# 06_Clock_Configuration.net
KiCad netlist of a schematic drawn in Altium Designer
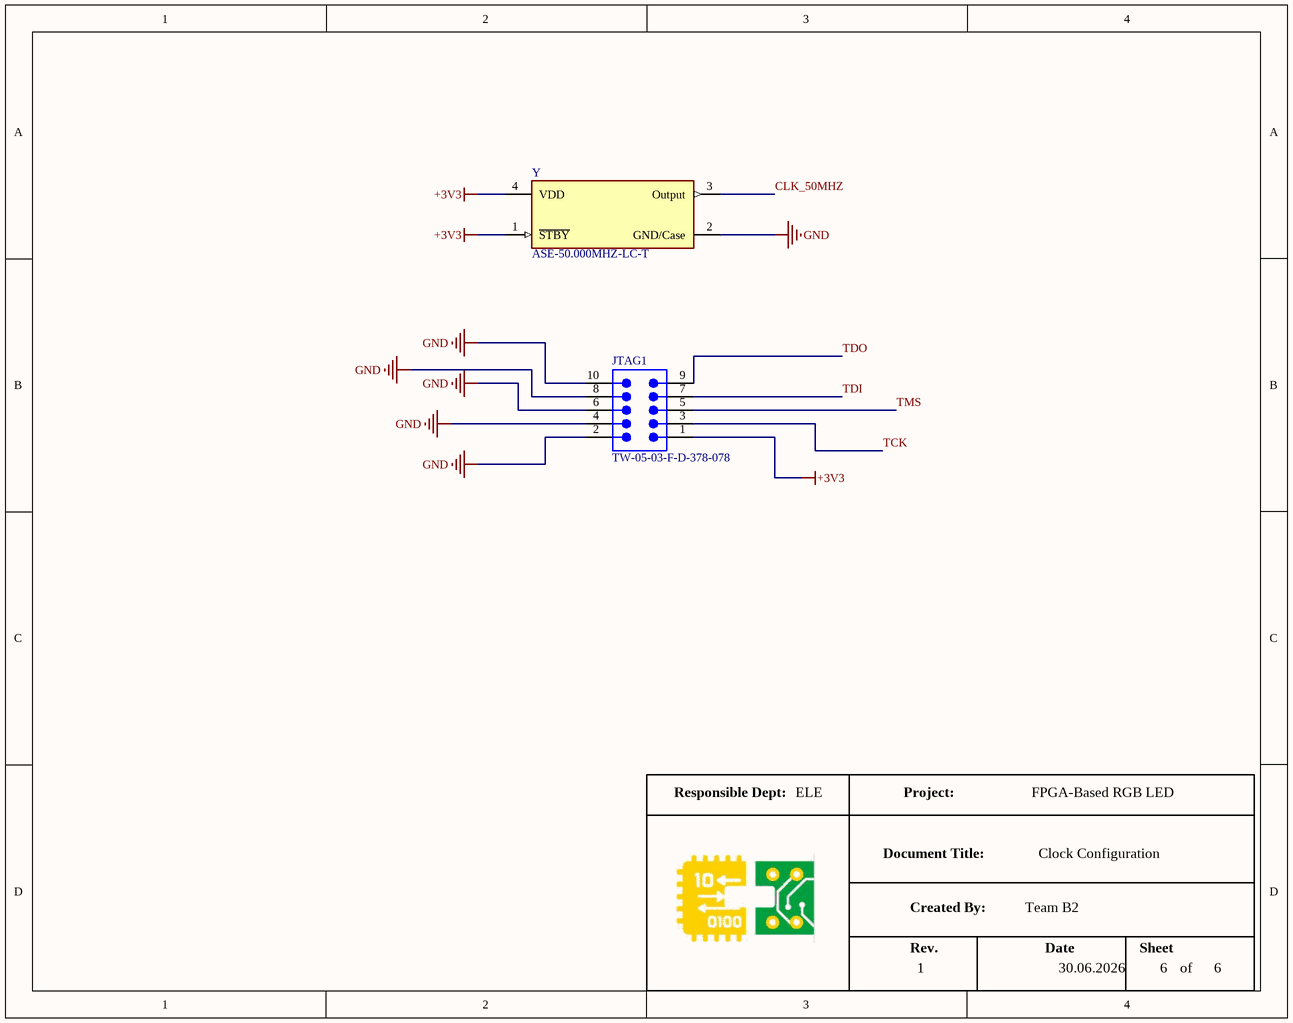
[diagram p0: 06_Clock_Configuration.SchDoc]

(export (version "E")
  (design (tool "Eeschema 10.0.6"))
  (components
    (comp (ref "JTAG1")
      (value "TW-05-03-F-D-378-078")
      (footprint "SMTC-TW-05-03-X-D-378-078")
      (description "Through-Hole Board Stacker, Vertical, -55 to 125 degC, 2 mm Pitch, 10-Pin, Male, RoHS")
      (fields (field (name "MANUFACTURER") "Samtec"))
      (libsource (lib "Altium Content Vault") (part "SMTC-TW-05-X-X-D"))
    )
    (comp (ref "Y")
      (value "ASE-50.000MHZ-LC-T")
      (footprint "FP-ASE-MFG")
      (description "XTAL Oscillator 50MHz ±50ppm CMOS 3.3V 4-SMD 3.2mm x 2.5mm")
      (libsource (lib "Altium Content Vault") (part "61a724e6190563596ac712fef61ad37"))
    )
  )
  (nets
    (net (code "1") (name "+3V3") (class "Default")
      (node (ref "JTAG1") (pin "1") (pinfunction "1_1") (pintype "passive"))
      (node (ref "Y") (pin "1") (pinfunction "~{STBY}_1") (pintype "input"))
      (node (ref "Y") (pin "4") (pinfunction "VDD_4") (pintype "power_in"))
    )
    (net (code "2") (name "/CLK_50MHZ") (class "Default")
      (node (ref "Y") (pin "3") (pinfunction "Output_3") (pintype "output"))
    )
    (net (code "3") (name "/TCK") (class "Default")
      (node (ref "JTAG1") (pin "3") (pinfunction "3_3") (pintype "passive"))
    )
    (net (code "4") (name "/TDI") (class "Default")
      (node (ref "JTAG1") (pin "7") (pinfunction "7_7") (pintype "passive"))
    )
    (net (code "5") (name "/TDO") (class "Default")
      (node (ref "JTAG1") (pin "9") (pinfunction "9_9") (pintype "passive"))
    )
    (net (code "6") (name "/TMS") (class "Default")
      (node (ref "JTAG1") (pin "5") (pinfunction "5_5") (pintype "passive"))
    )
    (net (code "7") (name "GND") (class "Default")
      (node (ref "JTAG1") (pin "10") (pinfunction "10_10") (pintype "passive"))
      (node (ref "JTAG1") (pin "2") (pinfunction "2_2") (pintype "passive"))
      (node (ref "JTAG1") (pin "4") (pinfunction "4_4") (pintype "passive"))
      (node (ref "JTAG1") (pin "6") (pinfunction "6_6") (pintype "passive"))
      (node (ref "JTAG1") (pin "8") (pinfunction "8_8") (pintype "passive"))
      (node (ref "Y") (pin "2") (pinfunction "GND/Case_2") (pintype "power_in"))
    )
  )
)
